# Relay_IO.net
KiCad netlist of a schematic drawn in Altium Designer
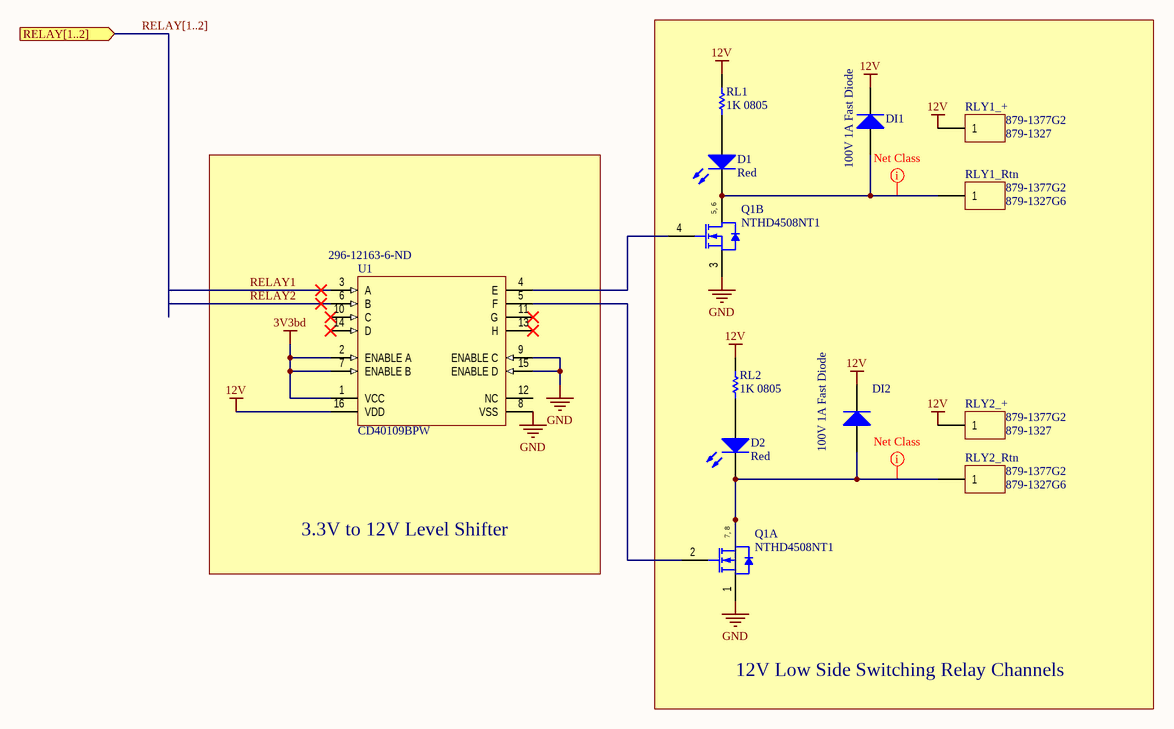
[diagram p0: Relay_IO.SchDoc]

(export (version "E")
  (design (tool "Eeschema 10.0.6"))
  (components
    (comp (ref "D1")
      (value "LED Red")
      (footprint "0603_A")
      (description "SMD mono-color Chip LED, WL-SMCW, Red")
      (fields
        (field (name "COLOR") "Red")
        (field (name "MANUFACTURER") "Wurth Electronics Inc")
        (field (name "MANUFACTURER PART NUMBER") "150060RS75000")
      )
      (libsource (lib "WCT") (part "LED_Red0603"))
    )
    (comp (ref "D2")
      (value "LED Red")
      (footprint "0603_A")
      (description "SMD mono-color Chip LED, WL-SMCW, Red")
      (fields
        (field (name "COLOR") "Red")
        (field (name "MANUFACTURER") "Wurth Electronics Inc")
        (field (name "MANUFACTURER PART NUMBER") "150060RS75000")
      )
      (libsource (lib "WCT") (part "LED_Red0603"))
    )
    (comp (ref "DI1")
      (value "100V 1A Fast Diode")
      (footprint "DO-35")
      (description "High Conductance Fast Diode")
      (fields
        (field (name "MANUFACTURER") "ON Semiconductor")
        (field (name "MANUFACTURER PART NUMBER") "MUR110RLG")
      )
      (libsource (lib "WCT") (part "Diode 1N4148"))
    )
    (comp (ref "DI2")
      (value "100V 1A Fast Diode")
      (footprint "DO-35")
      (description "High Conductance Fast Diode")
      (fields
        (field (name "MANUFACTURER") "ON Semiconductor")
        (field (name "MANUFACTURER PART NUMBER") "MUR110RLG")
      )
      (libsource (lib "WCT") (part "Diode 1N4148"))
    )
    (comp (ref "Q1")
      (value "NTHD4508NT1")
      (footprint "ONSC-CHIPFET-8-1206A-03_S2_V")
      (description "Power MOSFET, 20 V, 4.1 A, Dual N-Channel, 8-Pin CHIPFET, Tape and Reel")
      (fields
        (field (name "MANUFACTURER") "On Semiconductor")
        (field (name "MANUFACTURER PART NUMBER") "NTHD4508NT1G")
      )
      (libsource (lib "WCT") (part "NTHD4508NT1"))
    )
    (comp (ref "RL1")
      (value "1K 0805")
      (footprint "0805_L")
      (fields
        (field (name "MANUFACTURER") "Panasonic Electronic Components")
        (field (name "MANUFACTURER PART NUMBER") "ERJ-6GEYJ102V")
        (field (name "TOLERANCE") "±5%")
      )
      (libsource (lib "ICEdigikey") (part "Res1K_0805"))
    )
    (comp (ref "RL2")
      (value "1K 0805")
      (footprint "0805_L")
      (fields
        (field (name "MANUFACTURER") "Panasonic Electronic Components")
        (field (name "MANUFACTURER PART NUMBER") "ERJ-6GEYJ102V")
        (field (name "TOLERANCE") "±5%")
      )
      (libsource (lib "ICEdigikey") (part "Res1K_0805"))
    )
    (comp (ref "RLY1_+")
      (value "Anderson-1Pin RED_PCB_RHT")
      (footprint "Anderson_Red_RHT_BOT")
      (description "1 pin Anderson")
      (fields
        (field (name "MANUFACTURER") "Anderson Power Products (APP)")
        (field (name "MANUFACTURER PART NUMBER") "1377G1, 1377G2, 1327-BK,137G6-BK")
        (field (name "SUPPLIER PART NUMBER 1") "879-1377G2")
        (field (name "SUPPLIER PART NUMBER 2") "879-1327")
      )
      (libsource (lib "WCT") (part "Anderson-1Pin RED_PCB_RHT"))
    )
    (comp (ref "RLY1_Rtn")
      (value "Anderson-1Pin BLK_PCB_RHT")
      (footprint "Anderson_BLK_RHT_BOT")
      (description "1 pin Anderson")
      (fields
        (field (name "MANUFACTURER") "Anderson Power Products (APP)")
        (field (name "MANUFACTURER PART NUMBER") "1377G1, 1377G2, 1327-BK,137G6-BK")
        (field (name "SUPPLIER PART NUMBER 1") "879-1377G2")
        (field (name "SUPPLIER PART NUMBER 2") "879-1327G6")
      )
      (libsource (lib "WCT") (part "Anderson-1Pin BLK_PCB_RHT"))
    )
    (comp (ref "RLY2_+")
      (value "Anderson-1Pin RED_PCB_RHT")
      (footprint "Anderson_Red_RHT_BOT")
      (description "1 pin Anderson")
      (fields
        (field (name "MANUFACTURER") "Anderson Power Products (APP)")
        (field (name "MANUFACTURER PART NUMBER") "1377G1, 1377G2, 1327-BK,137G6-BK")
        (field (name "SUPPLIER PART NUMBER 1") "879-1377G2")
        (field (name "SUPPLIER PART NUMBER 2") "879-1327")
      )
      (libsource (lib "WCT") (part "Anderson-1Pin RED_PCB_RHT"))
    )
    (comp (ref "RLY2_Rtn")
      (value "Anderson-1Pin BLK_PCB_RHT")
      (footprint "Anderson_BLK_RHT_BOT")
      (description "1 pin Anderson")
      (fields
        (field (name "MANUFACTURER") "Anderson Power Products (APP)")
        (field (name "MANUFACTURER PART NUMBER") "1377G1, 1377G2, 1327-BK,137G6-BK")
        (field (name "SUPPLIER PART NUMBER 1") "879-1377G2")
        (field (name "SUPPLIER PART NUMBER 2") "879-1327G6")
      )
      (libsource (lib "WCT") (part "Anderson-1Pin BLK_PCB_RHT"))
    )
    (comp (ref "U1")
      (value "CD40109BPW")
      (footprint "PW0016A_M")
      (fields
        (field (name "MANUFACTURER") "Texas Instruments")
        (field (name "SUPPLIER PART NUMBER 1") "296-12163-6-ND")
        (field (name "MANUFACTURER PART NUMBER") "CD40109BPWR")
      )
      (libsource (lib "Altium Content Vault") (part "CMP-1527-00010-2"))
    )
  )
  (nets
    (net (code "1") (name "/RELAY1") (class "Default")
      (node (ref "U1") (pin "3") (pinfunction "A_3") (pintype "input"))
    )
    (net (code "2") (name "/RELAY2") (class "Default")
      (node (ref "U1") (pin "6") (pinfunction "B_6") (pintype "input"))
    )
    (net (code "4") (name "3V3bd") (class "Default")
      (node (ref "U1") (pin "1") (pinfunction "VCC_1") (pintype "power_in"))
      (node (ref "U1") (pin "2") (pinfunction "ENABLE_A_2") (pintype "input"))
      (node (ref "U1") (pin "7") (pinfunction "ENABLE_B_7") (pintype "input"))
    )
    (net (code "5") (name "12V") (class "Default")
      (node (ref "DI1") (pin "2") (pinfunction "K_2") (pintype "passive"))
      (node (ref "DI2") (pin "2") (pinfunction "K_2") (pintype "passive"))
      (node (ref "RL1") (pin "2") (pinfunction "2_2") (pintype "passive"))
      (node (ref "RL2") (pin "2") (pinfunction "2_2") (pintype "passive"))
      (node (ref "RLY1_+") (pin "1") (pinfunction "1_1") (pintype "passive"))
      (node (ref "RLY2_+") (pin "1") (pinfunction "1_1") (pintype "passive"))
      (node (ref "U1") (pin "16") (pinfunction "VDD_16") (pintype "power_in"))
    )
    (net (code "6") (name "GND") (class "Default")
      (node (ref "Q1") (pin "1") (pinfunction "S1_1") (pintype "passive"))
      (node (ref "Q1") (pin "3") (pinfunction "S2_3") (pintype "passive"))
      (node (ref "U1") (pin "15") (pinfunction "ENABLE_D_15") (pintype "input"))
      (node (ref "U1") (pin "8") (pinfunction "VSS_8") (pintype "power_in"))
      (node (ref "U1") (pin "9") (pinfunction "ENABLE_C_9") (pintype "input"))
    )
    (net (code "7") (name "Net-(D1-A)") (class "Default")
      (node (ref "D1") (pin "2") (pinfunction "A_2") (pintype "passive"))
      (node (ref "RL1") (pin "1") (pinfunction "1_1") (pintype "passive"))
    )
    (net (code "8") (name "Net-(D1-K)") (class "Default")
      (node (ref "D1") (pin "1") (pinfunction "K_1") (pintype "passive"))
      (node (ref "DI1") (pin "1") (pinfunction "A_1") (pintype "passive"))
      (node (ref "Q1") (pin "5") (pinfunction "D2_5") (pintype "passive"))
      (node (ref "Q1") (pin "6") (pinfunction "D2_6") (pintype "passive"))
      (node (ref "RLY1_Rtn") (pin "1") (pinfunction "1_1") (pintype "passive"))
    )
    (net (code "9") (name "Net-(D2-A)") (class "Default")
      (node (ref "D2") (pin "2") (pinfunction "A_2") (pintype "passive"))
      (node (ref "RL2") (pin "1") (pinfunction "1_1") (pintype "passive"))
    )
    (net (code "10") (name "Net-(D2-K)") (class "Default")
      (node (ref "D2") (pin "1") (pinfunction "K_1") (pintype "passive"))
      (node (ref "DI2") (pin "1") (pinfunction "A_1") (pintype "passive"))
      (node (ref "Q1") (pin "7") (pinfunction "D1_7") (pintype "passive"))
      (node (ref "Q1") (pin "8") (pinfunction "D1_8") (pintype "passive"))
      (node (ref "RLY2_Rtn") (pin "1") (pinfunction "1_1") (pintype "passive"))
    )
    (net (code "11") (name "Net-(Q1A-G1)") (class "Default")
      (node (ref "Q1") (pin "2") (pinfunction "G1_2") (pintype "passive"))
      (node (ref "U1") (pin "5") (pinfunction "F_5") (pintype "tri_state"))
    )
    (net (code "12") (name "Net-(Q1B-G2)") (class "Default")
      (node (ref "Q1") (pin "4") (pinfunction "G2_4") (pintype "passive"))
      (node (ref "U1") (pin "4") (pinfunction "E_4") (pintype "tri_state"))
    )
    (net (code "13") (name "unconnected-(U1-C-Pad10)") (class "Default")
      (node (ref "U1") (pin "10") (pinfunction "C_10") (pintype "input+no_connect"))
    )
    (net (code "14") (name "unconnected-(U1-D-Pad14)") (class "Default")
      (node (ref "U1") (pin "14") (pinfunction "D_14") (pintype "input+no_connect"))
    )
    (net (code "15") (name "unconnected-(U1-G-Pad11)") (class "Default")
      (node (ref "U1") (pin "11") (pinfunction "G_11") (pintype "tri_state+no_connect"))
    )
    (net (code "16") (name "unconnected-(U1-H-Pad13)") (class "Default")
      (node (ref "U1") (pin "13") (pinfunction "H_13") (pintype "tri_state+no_connect"))
    )
    (net (code "17") (name "unconnected-(U1-NC-Pad12)") (class "Default")
      (node (ref "U1") (pin "12") (pinfunction "NC_12") (pintype "passive"))
    )
  )
)
